# New.net
KiCad netlist of a schematic drawn in EAGLE
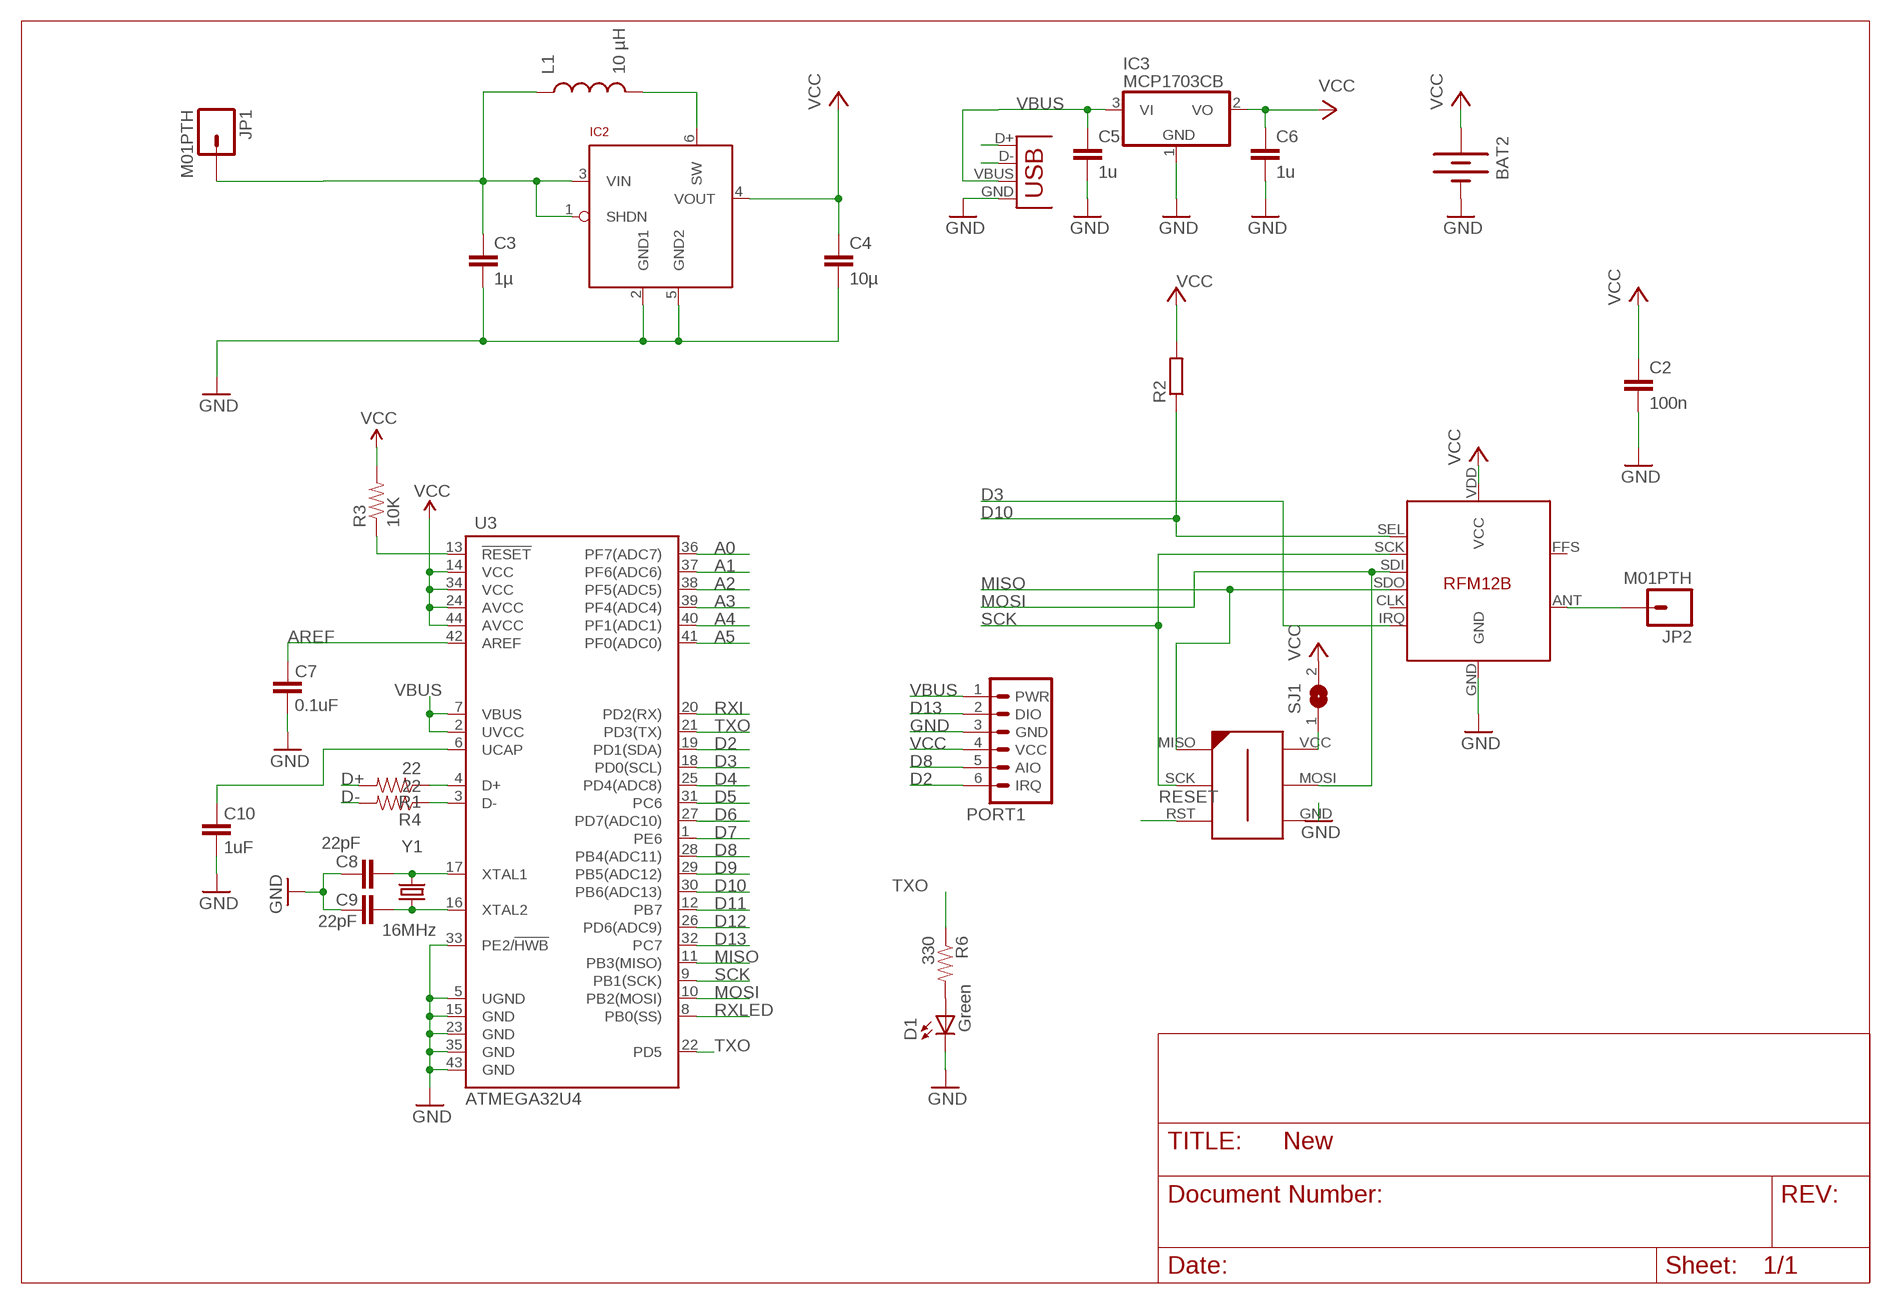
[diagram p0: schematic, sheet 1]

(export (version "E")
  (design (tool "Eeschema 10.0.6"))
  (components
    (comp (ref "BAT2")
      (value "BATTERY20PTH")
      (footprint "eagle-import:BATTCOM_20MM_PTH")
      (libsource (lib "eagle-import") (part "BATTERY20PTH"))
    )
    (comp (ref "C2")
      (value "100n")
      (footprint "eagle-import:C0603K")
      (libsource (lib "eagle-import") (part "C-EUC0603K"))
    )
    (comp (ref "C3")
      (value "1µ")
      (footprint "eagle-import:0603-CAP")
      (libsource (lib "eagle-import") (part "CAP0603-CAP"))
    )
    (comp (ref "C4")
      (value "10µ")
      (footprint "eagle-import:0805")
      (libsource (lib "eagle-import") (part "CAP0805"))
    )
    (comp (ref "C5")
      (value "1u")
      (footprint "eagle-import:C0603K")
      (libsource (lib "eagle-import") (part "C-EUC0603K"))
    )
    (comp (ref "C6")
      (value "1u")
      (footprint "eagle-import:C0603K")
      (libsource (lib "eagle-import") (part "C-EUC0603K"))
    )
    (comp (ref "C7")
      (value "0.1uF")
      (footprint "eagle-import:0402-CAP")
      (libsource (lib "eagle-import") (part "CAP0402-CAP"))
    )
    (comp (ref "C8")
      (value "22pF")
      (footprint "eagle-import:0402-CAP")
      (libsource (lib "eagle-import") (part "CAP0402-CAP"))
    )
    (comp (ref "C9")
      (value "22pF")
      (footprint "eagle-import:0402-CAP")
      (libsource (lib "eagle-import") (part "CAP0402-CAP"))
    )
    (comp (ref "C10")
      (value "1uF")
      (footprint "eagle-import:0402-CAP")
      (libsource (lib "eagle-import") (part "CAP0402-CAP"))
    )
    (comp (ref "D1")
      (value "Green")
      (footprint "eagle-import:LED-0603")
      (libsource (lib "eagle-import") (part "LED0603"))
    )
    (comp (ref "IC2")
      (value "LTC3525")
      (footprint "eagle-import:SC70")
      (libsource (lib "eagle-import") (part "LTC3525"))
    )
    (comp (ref "IC3")
      (value "MCP1703CB")
      (footprint "eagle-import:SOT23")
      (libsource (lib "eagle-import") (part "MCP1703CB"))
    )
    (comp (ref "JP1")
      (value "M01PTH")
      (footprint "eagle-import:1X01")
      (libsource (lib "eagle-import") (part "M01PTH"))
    )
    (comp (ref "JP2")
      (value "M01PTH")
      (footprint "eagle-import:1X01")
      (libsource (lib "eagle-import") (part "M01PTH"))
    )
    (comp (ref "L1")
      (value "10 µH")
      (footprint "eagle-import:1210")
      (libsource (lib "eagle-import") (part "INDUCTOR1210"))
    )
    (comp (ref "PORT1")
      (value "JEEPORT-FEMALE")
      (footprint "eagle-import:1X06_FEMALE_LOCK.010")
      (libsource (lib "eagle-import") (part "JEEPORT-FEMALE"))
    )
    (comp (ref "R1")
      (value "22")
      (footprint "eagle-import:0402-RES")
      (libsource (lib "eagle-import") (part "RESISTOR0402-RES"))
    )
    (comp (ref "R2")
      (value "R-EU_R0402")
      (footprint "eagle-import:R0402")
      (libsource (lib "eagle-import") (part "R-EU_R0402"))
    )
    (comp (ref "R3")
      (value "10K")
      (footprint "eagle-import:0402-RES")
      (libsource (lib "eagle-import") (part "RESISTOR0402-RES"))
    )
    (comp (ref "R4")
      (value "22")
      (footprint "eagle-import:0402-RES")
      (libsource (lib "eagle-import") (part "RESISTOR0402-RES"))
    )
    (comp (ref "R6")
      (value "330")
      (footprint "eagle-import:0402-RES")
      (libsource (lib "eagle-import") (part "RESISTOR0402-RES"))
    )
    (comp (ref "SJ1") (value "SJ") (footprint "eagle-import:SJ") (libsource (lib "eagle-import") (part "SJ")))
    (comp (ref "U$1")
      (value "RFM12B")
      (footprint "eagle-import:RFM12B")
      (libsource (lib "eagle-import") (part "RFM12B"))
    )
    (comp (ref "U$2")
      (value "AVR-ISP-6-EDGE")
      (footprint "eagle-import:6PAD_ISP")
      (libsource (lib "eagle-import") (part "AVR-ISP-6-EDGE"))
    )
    (comp (ref "U3")
      (value "ATMEGA32U4")
      (footprint "eagle-import:QFN-44-NOPAD")
      (libsource (lib "eagle-import") (part "ATMEGA32U4QFN2"))
    )
    (comp (ref "X1")
      (value "USB-MICROB")
      (footprint "eagle-import:USB-MICROB")
      (libsource (lib "eagle-import") (part "USB-MICROB"))
    )
    (comp (ref "Y1")
      (value "16MHz")
      (footprint "eagle-import:CRYSTAL-SMD-5X3")
      (libsource (lib "eagle-import") (part "CRYSTAL5X3"))
    )
  )
  (nets
    (net (code "1") (name "/A0") (class "Default")
      (node (ref "U3") (pin "36") (pinfunction "PF7(ADC7)_36") (pintype "bidirectional"))
    )
    (net (code "2") (name "/A1") (class "Default")
      (node (ref "U3") (pin "37") (pinfunction "PF6(ADC6)_37") (pintype "bidirectional"))
    )
    (net (code "3") (name "/A2") (class "Default")
      (node (ref "U3") (pin "38") (pinfunction "PF5(ADC5)_38") (pintype "bidirectional"))
    )
    (net (code "4") (name "/A3") (class "Default")
      (node (ref "U3") (pin "39") (pinfunction "PF4(ADC4)_39") (pintype "bidirectional"))
    )
    (net (code "5") (name "/A4") (class "Default")
      (node (ref "U3") (pin "40") (pinfunction "PF1(ADC1)_40") (pintype "bidirectional"))
    )
    (net (code "6") (name "/A5") (class "Default")
      (node (ref "U3") (pin "41") (pinfunction "PF0(ADC0)_41") (pintype "bidirectional"))
    )
    (net (code "7") (name "/AREF") (class "Default")
      (node (ref "C7") (pin "2") (pinfunction "2_2") (pintype "passive"))
      (node (ref "U3") (pin "42") (pinfunction "AREF_42") (pintype "bidirectional"))
    )
    (net (code "8") (name "/D+") (class "Default")
      (node (ref "R1") (pin "2") (pinfunction "2_2") (pintype "passive"))
      (node (ref "X1") (pin "D+") (pinfunction "D+_D+") (pintype "bidirectional"))
    )
    (net (code "9") (name "/D-") (class "Default")
      (node (ref "R4") (pin "2") (pinfunction "2_2") (pintype "passive"))
      (node (ref "X1") (pin "D-") (pinfunction "D-_D-") (pintype "bidirectional"))
    )
    (net (code "10") (name "/D2") (class "Default")
      (node (ref "PORT1") (pin "6") (pinfunction "IRQ_6") (pintype "bidirectional"))
      (node (ref "U3") (pin "19") (pinfunction "PD1(SDA)_19") (pintype "bidirectional"))
    )
    (net (code "11") (name "/D3") (class "Default")
      (node (ref "U$1") (pin "IRQ") (pinfunction "IRQ_IRQ") (pintype "open_collector"))
      (node (ref "U3") (pin "18") (pinfunction "PD0(SCL)_18") (pintype "bidirectional"))
    )
    (net (code "12") (name "/D4") (class "Default")
      (node (ref "U3") (pin "25") (pinfunction "PD4(ADC8)_25") (pintype "bidirectional"))
    )
    (net (code "13") (name "/D5") (class "Default")
      (node (ref "U3") (pin "31") (pinfunction "PC6_31") (pintype "bidirectional"))
    )
    (net (code "14") (name "/D6") (class "Default")
      (node (ref "U3") (pin "27") (pinfunction "PD7(ADC10)_27") (pintype "bidirectional"))
    )
    (net (code "15") (name "/D7") (class "Default")
      (node (ref "U3") (pin "1") (pinfunction "PE6_1") (pintype "bidirectional"))
    )
    (net (code "16") (name "/D8") (class "Default")
      (node (ref "PORT1") (pin "5") (pinfunction "AIO_5") (pintype "bidirectional"))
      (node (ref "U3") (pin "28") (pinfunction "PB4(ADC11)_28") (pintype "bidirectional"))
    )
    (net (code "17") (name "/D9") (class "Default")
      (node (ref "U3") (pin "29") (pinfunction "PB5(ADC12)_29") (pintype "bidirectional"))
    )
    (net (code "18") (name "/D10") (class "Default")
      (node (ref "R2") (pin "1") (pinfunction "1_1") (pintype "passive"))
      (node (ref "U$1") (pin "SEL") (pinfunction "SEL_SEL") (pintype "input"))
      (node (ref "U3") (pin "30") (pinfunction "PB6(ADC13)_30") (pintype "bidirectional"))
    )
    (net (code "19") (name "/D11") (class "Default")
      (node (ref "U3") (pin "12") (pinfunction "PB7_12") (pintype "bidirectional"))
    )
    (net (code "20") (name "/D12") (class "Default")
      (node (ref "U3") (pin "26") (pinfunction "PD6(ADC9)_26") (pintype "bidirectional"))
    )
    (net (code "21") (name "/D13") (class "Default")
      (node (ref "PORT1") (pin "2") (pinfunction "DIO_2") (pintype "bidirectional"))
      (node (ref "U3") (pin "32") (pinfunction "PC7_32") (pintype "bidirectional"))
    )
    (net (code "22") (name "/MISO") (class "Default")
      (node (ref "U$1") (pin "SDO") (pinfunction "SDO_SDO") (pintype "output"))
      (node (ref "U$2") (pin "MISO") (pinfunction "P$1_MISO") (pintype "bidirectional"))
      (node (ref "U3") (pin "11") (pinfunction "PB3(MISO)_11") (pintype "bidirectional"))
    )
    (net (code "23") (name "/MOSI") (class "Default")
      (node (ref "U$1") (pin "SDI") (pinfunction "SDI_SDI") (pintype "input"))
      (node (ref "U$2") (pin "MOSI") (pinfunction "P$5_MOSI") (pintype "bidirectional"))
      (node (ref "U3") (pin "10") (pinfunction "PB2(MOSI)_10") (pintype "bidirectional"))
    )
    (net (code "24") (name "/RESET") (class "Default")
      (node (ref "R3") (pin "1") (pinfunction "1_1") (pintype "passive"))
      (node (ref "U$2") (pin "RST") (pinfunction "P$3_RST") (pintype "bidirectional"))
      (node (ref "U3") (pin "13") (pinfunction "~{RESET}_13") (pintype "bidirectional"))
    )
    (net (code "25") (name "/RXI") (class "Default")
      (node (ref "U3") (pin "20") (pinfunction "PD2(RX)_20") (pintype "bidirectional"))
    )
    (net (code "26") (name "/RXLED") (class "Default")
      (node (ref "U3") (pin "8") (pinfunction "PB0(SS)_8") (pintype "bidirectional"))
    )
    (net (code "27") (name "/SCK") (class "Default")
      (node (ref "U$1") (pin "SCK") (pinfunction "SCK_SCK") (pintype "input"))
      (node (ref "U$2") (pin "SCK") (pinfunction "P$2_SCK") (pintype "bidirectional"))
      (node (ref "U3") (pin "9") (pinfunction "PB1(SCK)_9") (pintype "bidirectional"))
    )
    (net (code "28") (name "/TXO") (class "Default")
      (node (ref "R6") (pin "1") (pinfunction "1_1") (pintype "passive"))
      (node (ref "U3") (pin "21") (pinfunction "PD3(TX)_21") (pintype "bidirectional"))
    )
    (net (code "29") (name "/VBUS") (class "Default")
      (node (ref "C5") (pin "1") (pinfunction "1_1") (pintype "passive"))
      (node (ref "IC3") (pin "3") (pinfunction "VI_3") (pintype "input"))
      (node (ref "PORT1") (pin "1") (pinfunction "PWR_1") (pintype "power_in"))
      (node (ref "U3") (pin "2") (pinfunction "UVCC_2") (pintype "bidirectional"))
      (node (ref "U3") (pin "7") (pinfunction "VBUS_7") (pintype "bidirectional"))
      (node (ref "X1") (pin "VBUS") (pinfunction "VBUS_VBUS") (pintype "bidirectional"))
    )
    (net (code "30") (name "GND") (class "Default")
      (node (ref "BAT2") (pin "2") (pinfunction "-_2") (pintype "power_in"))
      (node (ref "C10") (pin "1") (pinfunction "1_1") (pintype "passive"))
      (node (ref "C2") (pin "2") (pinfunction "2_2") (pintype "passive"))
      (node (ref "C3") (pin "2") (pinfunction "2_2") (pintype "passive"))
      (node (ref "C4") (pin "2") (pinfunction "2_2") (pintype "passive"))
      (node (ref "C5") (pin "2") (pinfunction "2_2") (pintype "passive"))
      (node (ref "C6") (pin "2") (pinfunction "2_2") (pintype "passive"))
      (node (ref "C7") (pin "1") (pinfunction "1_1") (pintype "passive"))
      (node (ref "C8") (pin "2") (pinfunction "2_2") (pintype "passive"))
      (node (ref "C9") (pin "2") (pinfunction "2_2") (pintype "passive"))
      (node (ref "D1") (pin "C") (pinfunction "C_C") (pintype "passive"))
      (node (ref "IC2") (pin "2") (pinfunction "GND1_2") (pintype "power_in"))
      (node (ref "IC2") (pin "5") (pinfunction "GND2_5") (pintype "power_in"))
      (node (ref "IC3") (pin "1") (pinfunction "GND_1") (pintype "passive"))
      (node (ref "PORT1") (pin "3") (pinfunction "GND_3") (pintype "power_in"))
      (node (ref "U$1") (pin "GND") (pinfunction "GND_GND") (pintype "power_in"))
      (node (ref "U$2") (pin "GND") (pinfunction "P$4_GND") (pintype "bidirectional"))
      (node (ref "U3") (pin "15") (pinfunction "GND_15") (pintype "bidirectional"))
      (node (ref "U3") (pin "23") (pinfunction "GND_23") (pintype "bidirectional"))
      (node (ref "U3") (pin "33") (pinfunction "PE2/~{HWB}_33") (pintype "bidirectional"))
      (node (ref "U3") (pin "35") (pinfunction "GND_35") (pintype "bidirectional"))
      (node (ref "U3") (pin "43") (pinfunction "GND_43") (pintype "bidirectional"))
      (node (ref "U3") (pin "5") (pinfunction "UGND_5") (pintype "bidirectional"))
      (node (ref "X1") (pin "GND") (pinfunction "GND_GND") (pintype "bidirectional"))
    )
    (net (code "31") (name "Net-(D1-PadA)") (class "Default")
      (node (ref "D1") (pin "A") (pinfunction "A_A") (pintype "passive"))
      (node (ref "R6") (pin "2") (pinfunction "2_2") (pintype "passive"))
    )
    (net (code "32") (name "Net-(IC2-SHDN)") (class "Default")
      (node (ref "C3") (pin "1") (pinfunction "1_1") (pintype "passive"))
      (node (ref "IC2") (pin "1") (pinfunction "SHDN_1") (pintype "input"))
      (node (ref "IC2") (pin "3") (pinfunction "VIN_3") (pintype "tri_state"))
      (node (ref "JP1") (pin "1") (pinfunction "1_1") (pintype "passive"))
      (node (ref "L1") (pin "1") (pinfunction "1_1") (pintype "passive"))
    )
    (net (code "33") (name "Net-(IC2-SW)") (class "Default")
      (node (ref "IC2") (pin "6") (pinfunction "SW_6") (pintype "power_in"))
      (node (ref "L1") (pin "2") (pinfunction "2_2") (pintype "passive"))
    )
    (net (code "34") (name "Net-(JP2-Pad1)") (class "Default")
      (node (ref "JP2") (pin "1") (pinfunction "1_1") (pintype "passive"))
      (node (ref "U$1") (pin "ANT") (pinfunction "ANT_ANT") (pintype "passive"))
    )
    (net (code "35") (name "Net-(U$2-P$6)") (class "Default")
      (node (ref "SJ1") (pin "1") (pinfunction "1_1") (pintype "passive"))
      (node (ref "U$2") (pin "VCC") (pinfunction "P$6_VCC") (pintype "bidirectional"))
    )
    (net (code "36") (name "Net-(U3-D+)") (class "Default")
      (node (ref "R1") (pin "1") (pinfunction "1_1") (pintype "passive"))
      (node (ref "U3") (pin "4") (pinfunction "D+_4") (pintype "bidirectional"))
    )
    (net (code "37") (name "Net-(U3-D-)") (class "Default")
      (node (ref "R4") (pin "1") (pinfunction "1_1") (pintype "passive"))
      (node (ref "U3") (pin "3") (pinfunction "D-_3") (pintype "bidirectional"))
    )
    (net (code "38") (name "Net-(U3-UCAP)") (class "Default")
      (node (ref "C10") (pin "2") (pinfunction "2_2") (pintype "passive"))
      (node (ref "U3") (pin "6") (pinfunction "UCAP_6") (pintype "bidirectional"))
    )
    (net (code "39") (name "Net-(U3-XTAL1)") (class "Default")
      (node (ref "C8") (pin "1") (pinfunction "1_1") (pintype "passive"))
      (node (ref "U3") (pin "17") (pinfunction "XTAL1_17") (pintype "bidirectional"))
      (node (ref "Y1") (pin "3") (pinfunction "2_3") (pintype "passive"))
    )
    (net (code "40") (name "Net-(U3-XTAL2)") (class "Default")
      (node (ref "C9") (pin "1") (pinfunction "1_1") (pintype "passive"))
      (node (ref "U3") (pin "16") (pinfunction "XTAL2_16") (pintype "bidirectional"))
      (node (ref "Y1") (pin "1") (pinfunction "1_1") (pintype "passive"))
    )
    (net (code "41") (name "VCC") (class "Default")
      (node (ref "BAT2") (pin "1") (pinfunction "+_1") (pintype "power_in"))
      (node (ref "C2") (pin "1") (pinfunction "1_1") (pintype "passive"))
      (node (ref "C4") (pin "1") (pinfunction "1_1") (pintype "passive"))
      (node (ref "C6") (pin "1") (pinfunction "1_1") (pintype "passive"))
      (node (ref "IC2") (pin "4") (pinfunction "VOUT_4") (pintype "power_in"))
      (node (ref "IC3") (pin "2") (pinfunction "VO_2") (pintype "passive"))
      (node (ref "PORT1") (pin "4") (pinfunction "VCC_4") (pintype "power_in"))
      (node (ref "R2") (pin "2") (pinfunction "2_2") (pintype "passive"))
      (node (ref "R3") (pin "2") (pinfunction "2_2") (pintype "passive"))
      (node (ref "SJ1") (pin "2") (pinfunction "2_2") (pintype "passive"))
      (node (ref "U$1") (pin "VDD") (pinfunction "VCC_VDD") (pintype "power_in"))
      (node (ref "U3") (pin "14") (pinfunction "VCC_14") (pintype "bidirectional"))
      (node (ref "U3") (pin "24") (pinfunction "AVCC_24") (pintype "bidirectional"))
      (node (ref "U3") (pin "34") (pinfunction "VCC_34") (pintype "bidirectional"))
      (node (ref "U3") (pin "44") (pinfunction "AVCC_44") (pintype "bidirectional"))
    )
    (net (code "42") (name "unconnected-(U$1-PadCLK)") (class "Default")
      (node (ref "U$1") (pin "CLK") (pinfunction "CLK_CLK") (pintype "output"))
    )
    (net (code "43") (name "unconnected-(U$1-PadFFS)") (class "Default")
      (node (ref "U$1") (pin "FFS") (pinfunction "FFS_FFS") (pintype "bidirectional"))
    )
    (net (code "44") (name "unconnected-(U3-PD5-Pad22)") (class "Default")
      (node (ref "U3") (pin "22") (pinfunction "PD5_22") (pintype "bidirectional"))
    )
  )
)
